# chip_mux_test.net
KiCad netlist of a schematic drawn in EAGLE
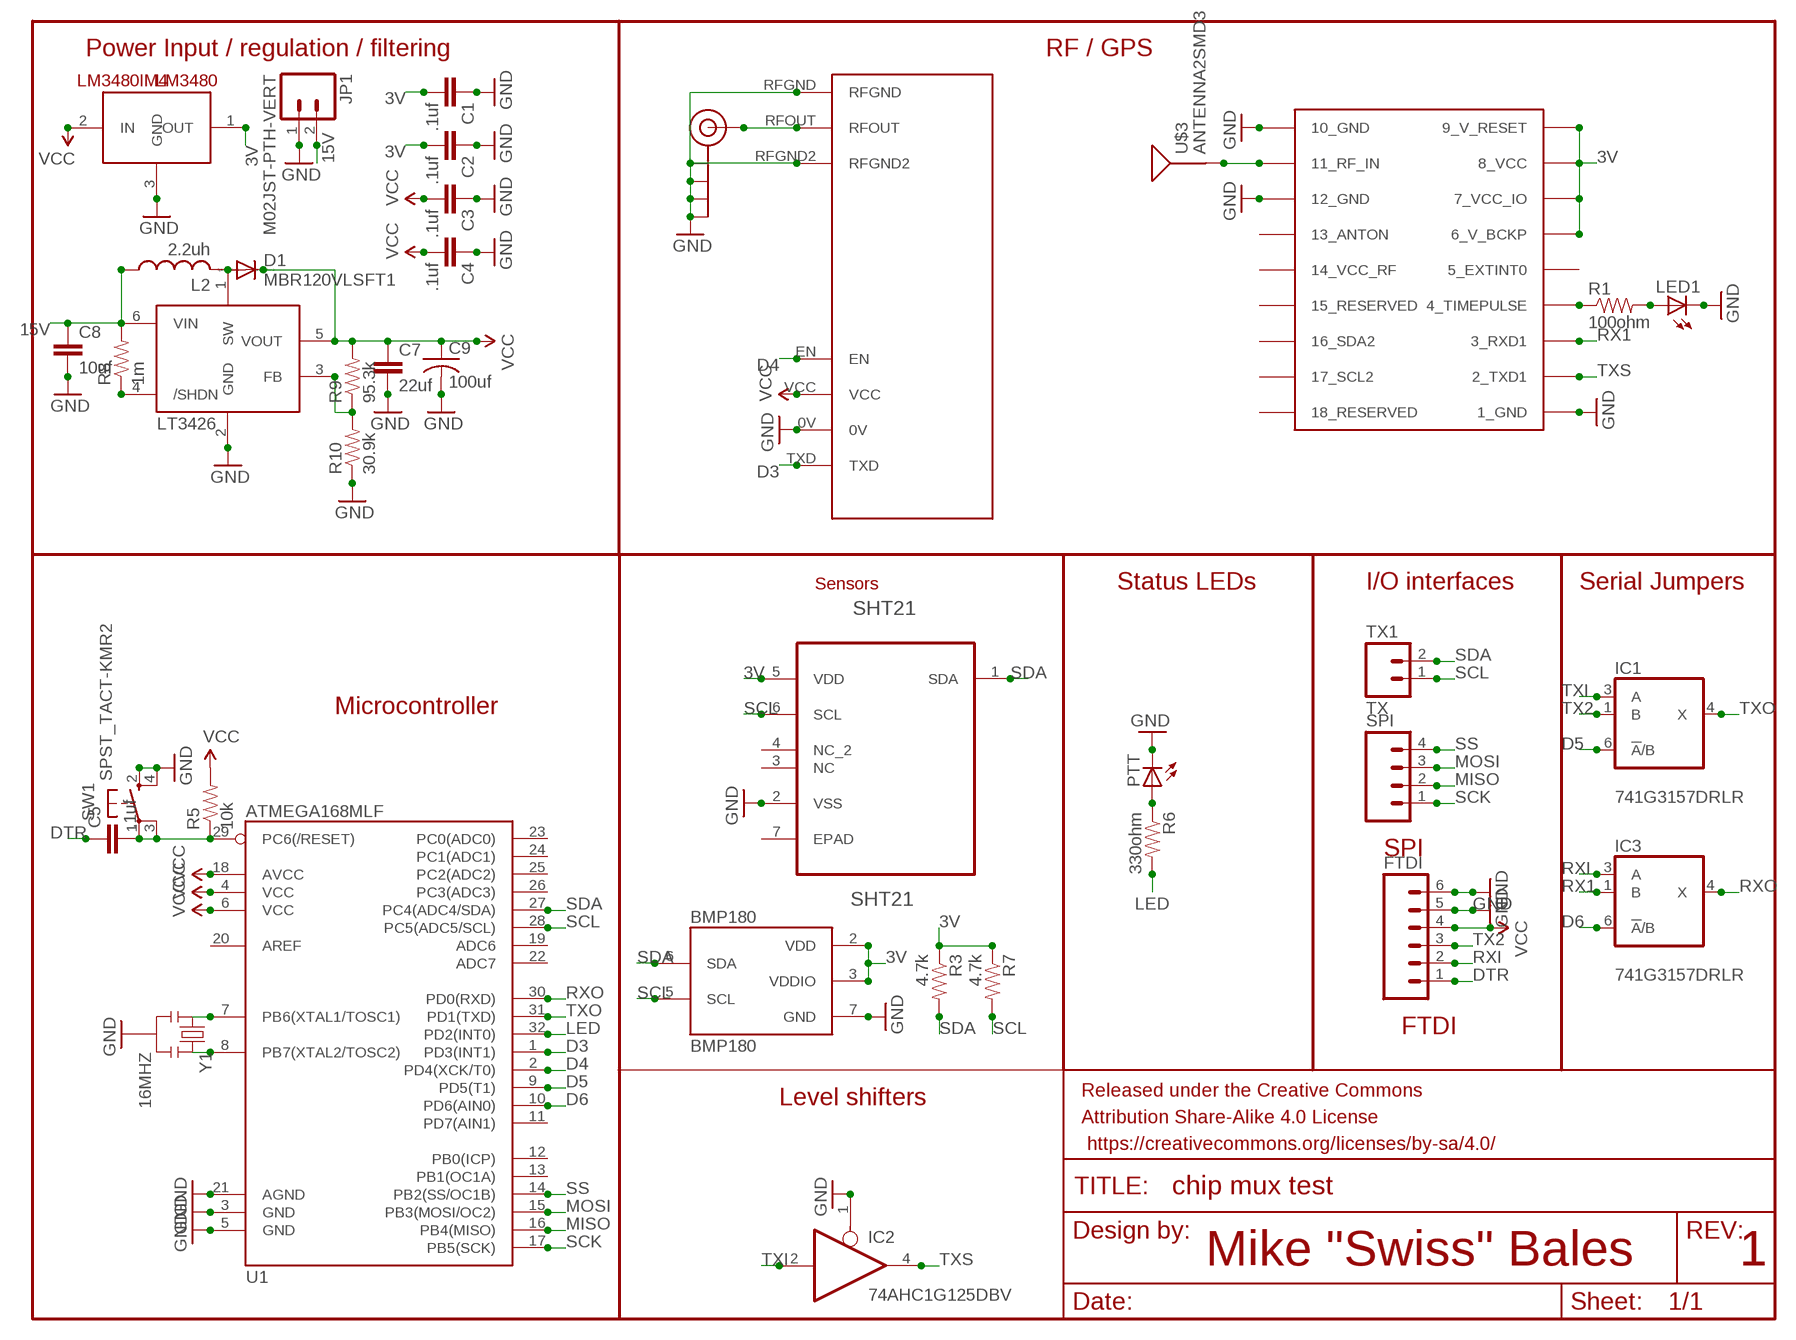
[diagram p0: schematic, sheet 1]

(export (version "E")
  (design (tool "Eeschema 10.0.6"))
  (components
    (comp (ref "BMP180")
      (value "BMP180")
      (footprint "eagle-import:BMP180")
      (libsource (lib "eagle-import") (part "BMP180"))
    )
    (comp (ref "C1")
      (value ".1uf")
      (footprint "eagle-import:0805")
      (libsource (lib "eagle-import") (part "CAP0805"))
    )
    (comp (ref "C2")
      (value ".1uf")
      (footprint "eagle-import:0805")
      (libsource (lib "eagle-import") (part "CAP0805"))
    )
    (comp (ref "C3")
      (value ".1uf")
      (footprint "eagle-import:0805")
      (libsource (lib "eagle-import") (part "CAP0805"))
    )
    (comp (ref "C4")
      (value ".1uf")
      (footprint "eagle-import:0805")
      (libsource (lib "eagle-import") (part "CAP0805"))
    )
    (comp (ref "C5")
      (value ".1uf")
      (footprint "eagle-import:0805")
      (libsource (lib "eagle-import") (part "CAP0805"))
    )
    (comp (ref "C7")
      (value "22uf")
      (footprint "eagle-import:0805")
      (libsource (lib "eagle-import") (part "CAP0805"))
    )
    (comp (ref "C8")
      (value "10uf")
      (footprint "eagle-import:0805")
      (libsource (lib "eagle-import") (part "CAP0805"))
    )
    (comp (ref "C9")
      (value "100uf")
      (footprint "eagle-import:C1206")
      (libsource (lib "eagle-import") (part "C-USC1206"))
    )
    (comp (ref "D1")
      (value "MBR120VLSFT1")
      (footprint "eagle-import:SOD123")
      (libsource (lib "eagle-import") (part "DIODE-SOD123"))
    )
    (comp (ref "FRAME1")
      (value "FRAME-LETTER")
      (footprint "eagle-import:CREATIVE_COMMONS")
      (libsource (lib "eagle-import") (part "FRAME-LETTER"))
    )
    (comp (ref "FTDI")
      (value "M06NO_SILK_FEMALE_PTH")
      (footprint "eagle-import:1X06_NO_SILK")
      (libsource (lib "eagle-import") (part "M06NO_SILK_FEMALE_PTH"))
    )
    (comp (ref "IC1")
      (value "741G3157DRLR")
      (footprint "eagle-import:DRL_R-PDSO-N6")
      (libsource (lib "eagle-import") (part "741G3157DRLR"))
    )
    (comp (ref "IC2")
      (value "74AHC1G125DBV")
      (footprint "eagle-import:SOT23-5")
      (libsource (lib "eagle-import") (part "741G125DBVAHC"))
    )
    (comp (ref "IC3")
      (value "741G3157DRLR")
      (footprint "eagle-import:DRL_R-PDSO-N6")
      (libsource (lib "eagle-import") (part "741G3157DRLR"))
    )
    (comp (ref "J$1")
      (value "SMA_EDGE")
      (footprint "eagle-import:SMA-EDGE")
      (libsource (lib "eagle-import") (part "SMA_EDGE"))
    )
    (comp (ref "JP1")
      (value "M02JST-PTH-VERT")
      (footprint "eagle-import:JST-2-PTH-VERT")
      (libsource (lib "eagle-import") (part "M02JST-PTH-VERT"))
    )
    (comp (ref "L2")
      (value "2.2uh")
      (footprint "eagle-import:L1812")
      (libsource (lib "eagle-import") (part "L-USL1812"))
    )
    (comp (ref "LED1")
      (value "LEDCHIP-LED0805")
      (footprint "eagle-import:CHIP-LED0805")
      (libsource (lib "eagle-import") (part "LEDCHIP-LED0805"))
    )
    (comp (ref "LM3480")
      (value "LM3480IM4")
      (footprint "eagle-import:SOT23-3")
      (libsource (lib "eagle-import") (part "LM3480IM4"))
    )
    (comp (ref "LT3426")
      (value "LT3426")
      (footprint "eagle-import:SOT23-6")
      (libsource (lib "eagle-import") (part "LT3426"))
    )
    (comp (ref "PTT")
      (value "LEDCHIP-LED0805")
      (footprint "eagle-import:CHIP-LED0805")
      (libsource (lib "eagle-import") (part "LEDCHIP-LED0805"))
    )
    (comp (ref "R1")
      (value "100ohm")
      (footprint "eagle-import:0805")
      (libsource (lib "eagle-import") (part "RESISTOR0805-RES"))
    )
    (comp (ref "R3")
      (value "4.7k")
      (footprint "eagle-import:0805")
      (libsource (lib "eagle-import") (part "RESISTOR0805-RES"))
    )
    (comp (ref "R5")
      (value "10k")
      (footprint "eagle-import:0805")
      (libsource (lib "eagle-import") (part "RESISTOR0805-RES"))
    )
    (comp (ref "R6")
      (value "330ohm")
      (footprint "eagle-import:0805")
      (libsource (lib "eagle-import") (part "RESISTOR0805-RES"))
    )
    (comp (ref "R7")
      (value "4.7k")
      (footprint "eagle-import:0805")
      (libsource (lib "eagle-import") (part "RESISTOR0805-RES"))
    )
    (comp (ref "R8")
      (value "1m")
      (footprint "eagle-import:0805")
      (libsource (lib "eagle-import") (part "RESISTOR0805-RES"))
    )
    (comp (ref "R9")
      (value "95.3k")
      (footprint "eagle-import:0805")
      (libsource (lib "eagle-import") (part "RESISTOR0805-RES"))
    )
    (comp (ref "R10")
      (value "30.9k")
      (footprint "eagle-import:0805")
      (libsource (lib "eagle-import") (part "RESISTOR0805-RES"))
    )
    (comp (ref "SHT21")
      (value "SHT21")
      (footprint "eagle-import:DFN300X300X110-7N")
      (libsource (lib "eagle-import") (part "SHT21"))
    )
    (comp (ref "SPI")
      (value "M04JST-PTH-VERT")
      (footprint "eagle-import:JST-4-PTH-VERT")
      (libsource (lib "eagle-import") (part "M04JST-PTH-VERT"))
    )
    (comp (ref "SW1")
      (value "SPST_TACT-KMR2")
      (footprint "eagle-import:KMR2")
      (libsource (lib "eagle-import") (part "SPST_TACT-KMR2"))
    )
    (comp (ref "TX1")
      (value "TX")
      (footprint "eagle-import:JST-2-PTH-VERT")
      (libsource (lib "eagle-import") (part "M02JST-PTH-VERT"))
    )
    (comp (ref "U$1")
      (value "UBLOX_MAX")
      (footprint "eagle-import:UBLOX_MAX")
      (libsource (lib "eagle-import") (part "UBLOX_MAX"))
    )
    (comp (ref "U$2")
      (value "RADIOMETRIX-HX1")
      (footprint "eagle-import:RADIOMETRIX-HX1")
      (libsource (lib "eagle-import") (part "RADIOMETRIX-HX1"))
    )
    (comp (ref "U$3")
      (value "ANTENNA2SMD3")
      (footprint "eagle-import:ANTENNA-CHIP4")
      (libsource (lib "eagle-import") (part "ANTENNA2SMD3"))
    )
    (comp (ref "U1")
      (value "ATMEGA168MLF")
      (footprint "eagle-import:MLF32")
      (libsource (lib "eagle-import") (part "ATMEGA168MLF"))
    )
    (comp (ref "Y1")
      (value "16MHZ")
      (footprint "eagle-import:RESONATOR-SMD")
      (libsource (lib "eagle-import") (part "RESONATOR16MHZ"))
    )
  )
  (nets
    (net (code "1") (name "/3V") (class "Default")
      (node (ref "BMP180") (pin "2") (pinfunction "VDD_2") (pintype "power_in"))
      (node (ref "BMP180") (pin "3") (pinfunction "VDDIO_3") (pintype "power_in"))
      (node (ref "C1") (pin "2") (pinfunction "2_2") (pintype "passive"))
      (node (ref "C2") (pin "2") (pinfunction "2_2") (pintype "passive"))
      (node (ref "LM3480") (pin "1") (pinfunction "OUT_1") (pintype "bidirectional"))
      (node (ref "R3") (pin "1") (pinfunction "1_1") (pintype "passive"))
      (node (ref "R7") (pin "1") (pinfunction "1_1") (pintype "passive"))
      (node (ref "SHT21") (pin "5") (pinfunction "VDD_5") (pintype "power_in"))
      (node (ref "U$1") (pin "6_V_BCKP") (pinfunction "6_V_BCKP_6_V_BCKP") (pintype "bidirectional"))
      (node (ref "U$1") (pin "7_VCC_IO") (pinfunction "7_VCC_IO_7_VCC_IO") (pintype "power_in"))
      (node (ref "U$1") (pin "8_VCC") (pinfunction "8_VCC_8_VCC") (pintype "power_in"))
      (node (ref "U$1") (pin "9_V_RESET") (pinfunction "9_V_RESET_9_V_RESET") (pintype "power_in"))
    )
    (net (code "2") (name "/15V") (class "Default")
      (node (ref "C8") (pin "1") (pinfunction "1_1") (pintype "passive"))
      (node (ref "JP1") (pin "2") (pinfunction "2_2") (pintype "passive"))
      (node (ref "L2") (pin "1") (pinfunction "1_1") (pintype "passive"))
      (node (ref "LT3426") (pin "6") (pinfunction "VIN_6") (pintype "input"))
      (node (ref "R8") (pin "2") (pinfunction "2_2") (pintype "passive"))
    )
    (net (code "3") (name "/D3") (class "Default")
      (node (ref "U$2") (pin "TXD") (pinfunction "TXD_TXD") (pintype "bidirectional"))
      (node (ref "U1") (pin "1") (pinfunction "PD3(INT1)_1") (pintype "bidirectional"))
    )
    (net (code "4") (name "/D4") (class "Default")
      (node (ref "U$2") (pin "EN") (pinfunction "EN_EN") (pintype "bidirectional"))
      (node (ref "U1") (pin "2") (pinfunction "PD4(XCK/T0)_2") (pintype "bidirectional"))
    )
    (net (code "5") (name "/D5") (class "Default")
      (node (ref "IC1") (pin "6") (pinfunction "~{A}/B_6") (pintype "input"))
      (node (ref "U1") (pin "9") (pinfunction "PD5(T1)_9") (pintype "bidirectional"))
    )
    (net (code "6") (name "/D6") (class "Default")
      (node (ref "IC3") (pin "6") (pinfunction "~{A}/B_6") (pintype "input"))
      (node (ref "U1") (pin "10") (pinfunction "PD6(AIN0)_10") (pintype "bidirectional"))
    )
    (net (code "7") (name "/DTR") (class "Default")
      (node (ref "C5") (pin "1") (pinfunction "1_1") (pintype "passive"))
      (node (ref "FTDI") (pin "1") (pinfunction "1_1") (pintype "passive"))
    )
    (net (code "8") (name "/LED") (class "Default")
      (node (ref "R6") (pin "2") (pinfunction "2_2") (pintype "passive"))
      (node (ref "U1") (pin "32") (pinfunction "PD2(INT0)_32") (pintype "bidirectional"))
    )
    (net (code "9") (name "/MISO") (class "Default")
      (node (ref "SPI") (pin "2") (pinfunction "2_2") (pintype "passive"))
      (node (ref "U1") (pin "16") (pinfunction "PB4(MISO)_16") (pintype "bidirectional"))
    )
    (net (code "10") (name "/MOSI") (class "Default")
      (node (ref "SPI") (pin "3") (pinfunction "3_3") (pintype "passive"))
      (node (ref "U1") (pin "15") (pinfunction "PB3(MOSI/OC2)_15") (pintype "bidirectional"))
    )
    (net (code "11") (name "/RX1") (class "Default")
      (node (ref "IC3") (pin "1") (pinfunction "B_1") (pintype "bidirectional"))
      (node (ref "U$1") (pin "3_RXD1") (pinfunction "3_RXD1_3_RXD1") (pintype "bidirectional"))
    )
    (net (code "12") (name "/RXI") (class "Default")
      (node (ref "FTDI") (pin "2") (pinfunction "2_2") (pintype "passive"))
      (node (ref "IC3") (pin "3") (pinfunction "A_3") (pintype "bidirectional"))
    )
    (net (code "13") (name "/RXO") (class "Default")
      (node (ref "IC3") (pin "4") (pinfunction "X_4") (pintype "bidirectional"))
      (node (ref "U1") (pin "30") (pinfunction "PD0(RXD)_30") (pintype "bidirectional"))
    )
    (net (code "14") (name "/SCK") (class "Default")
      (node (ref "SPI") (pin "1") (pinfunction "1_1") (pintype "passive"))
      (node (ref "U1") (pin "17") (pinfunction "PB5(SCK)_17") (pintype "bidirectional"))
    )
    (net (code "15") (name "/SCL") (class "Default")
      (node (ref "BMP180") (pin "5") (pinfunction "SCL_5") (pintype "input"))
      (node (ref "R7") (pin "2") (pinfunction "2_2") (pintype "passive"))
      (node (ref "SHT21") (pin "6") (pinfunction "SCL_6") (pintype "input"))
      (node (ref "TX1") (pin "1") (pinfunction "1_1") (pintype "passive"))
      (node (ref "U1") (pin "28") (pinfunction "PC5(ADC5/SCL)_28") (pintype "bidirectional"))
    )
    (net (code "16") (name "/SDA") (class "Default")
      (node (ref "BMP180") (pin "6") (pinfunction "SDA_6") (pintype "bidirectional"))
      (node (ref "R3") (pin "2") (pinfunction "2_2") (pintype "passive"))
      (node (ref "SHT21") (pin "1") (pinfunction "SDA_1") (pintype "bidirectional"))
      (node (ref "TX1") (pin "2") (pinfunction "2_2") (pintype "passive"))
      (node (ref "U1") (pin "27") (pinfunction "PC4(ADC4/SDA)_27") (pintype "bidirectional"))
    )
    (net (code "17") (name "/SS") (class "Default")
      (node (ref "SPI") (pin "4") (pinfunction "4_4") (pintype "passive"))
      (node (ref "U1") (pin "14") (pinfunction "PB2(SS/OC1B)_14") (pintype "bidirectional"))
    )
    (net (code "18") (name "/TX2") (class "Default")
      (node (ref "FTDI") (pin "3") (pinfunction "3_3") (pintype "passive"))
      (node (ref "IC1") (pin "1") (pinfunction "B_1") (pintype "bidirectional"))
    )
    (net (code "19") (name "/TXI") (class "Default")
      (node (ref "IC1") (pin "3") (pinfunction "A_3") (pintype "bidirectional"))
      (node (ref "IC2") (pin "2") (pinfunction "I_2") (pintype "input"))
    )
    (net (code "20") (name "/TXO") (class "Default")
      (node (ref "IC1") (pin "4") (pinfunction "X_4") (pintype "bidirectional"))
      (node (ref "U1") (pin "31") (pinfunction "PD1(TXD)_31") (pintype "bidirectional"))
    )
    (net (code "21") (name "/TXS") (class "Default")
      (node (ref "IC2") (pin "4") (pinfunction "O_4") (pintype "tri_state"))
      (node (ref "U$1") (pin "2_TXD1") (pinfunction "2_TXD1_2_TXD1") (pintype "bidirectional"))
    )
    (net (code "22") (name "GND") (class "Default")
      (node (ref "BMP180") (pin "7") (pinfunction "GND_7") (pintype "power_in"))
      (node (ref "C1") (pin "1") (pinfunction "1_1") (pintype "passive"))
      (node (ref "C2") (pin "1") (pinfunction "1_1") (pintype "passive"))
      (node (ref "C3") (pin "1") (pinfunction "1_1") (pintype "passive"))
      (node (ref "C4") (pin "1") (pinfunction "1_1") (pintype "passive"))
      (node (ref "C7") (pin "2") (pinfunction "2_2") (pintype "passive"))
      (node (ref "C8") (pin "2") (pinfunction "2_2") (pintype "passive"))
      (node (ref "C9") (pin "2") (pinfunction "2_2") (pintype "passive"))
      (node (ref "FTDI") (pin "5") (pinfunction "5_5") (pintype "passive"))
      (node (ref "FTDI") (pin "6") (pinfunction "6_6") (pintype "passive"))
      (node (ref "IC2") (pin "1") (pinfunction "OE_1") (pintype "input"))
      (node (ref "J$1") (pin "GND@0") (pinfunction "GND_GND@0") (pintype "bidirectional"))
      (node (ref "J$1") (pin "GND@1") (pinfunction "GND_GND@1") (pintype "bidirectional"))
      (node (ref "J$1") (pin "GND@2") (pinfunction "GND_GND@2") (pintype "bidirectional"))
      (node (ref "J$1") (pin "GND@3") (pinfunction "GND_GND@3") (pintype "bidirectional"))
      (node (ref "JP1") (pin "1") (pinfunction "1_1") (pintype "passive"))
      (node (ref "LED1") (pin "C") (pinfunction "C_C") (pintype "passive"))
      (node (ref "LM3480") (pin "3") (pinfunction "GND_3") (pintype "bidirectional"))
      (node (ref "LT3426") (pin "2") (pinfunction "GND_2") (pintype "power_in"))
      (node (ref "PTT") (pin "C") (pinfunction "C_C") (pintype "passive"))
      (node (ref "R10") (pin "1") (pinfunction "1_1") (pintype "passive"))
      (node (ref "SHT21") (pin "2") (pinfunction "VSS_2") (pintype "power_in"))
      (node (ref "SW1") (pin "2") (pinfunction "S_2") (pintype "passive"))
      (node (ref "SW1") (pin "4") (pinfunction "S1_4") (pintype "passive"))
      (node (ref "U$1") (pin "10_GND") (pinfunction "10_GND_10_GND") (pintype "power_in"))
      (node (ref "U$1") (pin "12_GND") (pinfunction "12_GND_12_GND") (pintype "power_in"))
      (node (ref "U$1") (pin "1_GND") (pinfunction "1_GND_1_GND") (pintype "power_in"))
      (node (ref "U$2") (pin "0V") (pinfunction "0V_0V") (pintype "bidirectional"))
      (node (ref "U$2") (pin "RFGND") (pinfunction "RFGND_RFGND") (pintype "bidirectional"))
      (node (ref "U$2") (pin "RFGND2") (pinfunction "RFGND2_RFGND2") (pintype "bidirectional"))
      (node (ref "U1") (pin "21") (pinfunction "AGND_21") (pintype "bidirectional"))
      (node (ref "U1") (pin "3") (pinfunction "GND_3") (pintype "bidirectional"))
      (node (ref "U1") (pin "5") (pinfunction "GND_5") (pintype "bidirectional"))
      (node (ref "Y1") (pin "2") (pinfunction "2_2") (pintype "passive"))
    )
    (net (code "23") (name "Net-(J$1-SIGNAL)") (class "Default")
      (node (ref "J$1") (pin "SIG") (pinfunction "SIGNAL_SIG") (pintype "bidirectional"))
      (node (ref "U$2") (pin "RFOUT") (pinfunction "RFOUT_RFOUT") (pintype "bidirectional"))
    )
    (net (code "24") (name "Net-(LED1-PadA)") (class "Default")
      (node (ref "LED1") (pin "A") (pinfunction "A_A") (pintype "passive"))
      (node (ref "R1") (pin "2") (pinfunction "2_2") (pintype "passive"))
    )
    (net (code "25") (name "Net-(LT3426-FB)") (class "Default")
      (node (ref "LT3426") (pin "3") (pinfunction "FB_3") (pintype "input"))
      (node (ref "R10") (pin "2") (pinfunction "2_2") (pintype "passive"))
      (node (ref "R9") (pin "1") (pinfunction "1_1") (pintype "passive"))
    )
    (net (code "26") (name "Net-(LT3426-SW)") (class "Default")
      (node (ref "D1") (pin "A") (pinfunction "A_A") (pintype "passive"))
      (node (ref "L2") (pin "2") (pinfunction "2_2") (pintype "passive"))
      (node (ref "LT3426") (pin "1") (pinfunction "SW_1") (pintype "output"))
    )
    (net (code "27") (name "Net-(LT3426-{slash}SHDN)") (class "Default")
      (node (ref "LT3426") (pin "4") (pinfunction "/SHDN_4") (pintype "input"))
      (node (ref "R8") (pin "1") (pinfunction "1_1") (pintype "passive"))
    )
    (net (code "28") (name "Net-(PTT-PadA)") (class "Default")
      (node (ref "PTT") (pin "A") (pinfunction "A_A") (pintype "passive"))
      (node (ref "R6") (pin "1") (pinfunction "1_1") (pintype "passive"))
    )
    (net (code "29") (name "Net-(R1-Pad1)") (class "Default")
      (node (ref "R1") (pin "1") (pinfunction "1_1") (pintype "passive"))
      (node (ref "U$1") (pin "4_TIMEPULSE") (pinfunction "4_TIMEPULSE_4_TIMEPULSE") (pintype "bidirectional"))
    )
    (net (code "30") (name "Net-(SW1-P)") (class "Default")
      (node (ref "C5") (pin "2") (pinfunction "2_2") (pintype "passive"))
      (node (ref "R5") (pin "1") (pinfunction "1_1") (pintype "passive"))
      (node (ref "SW1") (pin "1") (pinfunction "P_1") (pintype "passive"))
      (node (ref "SW1") (pin "3") (pinfunction "P1_3") (pintype "passive"))
      (node (ref "U1") (pin "29") (pinfunction "PC6(/RESET)_29") (pintype "bidirectional"))
    )
    (net (code "31") (name "Net-(U$3-SIGNAL)") (class "Default")
      (node (ref "U$1") (pin "11_RF_IN") (pinfunction "11_RF_IN_11_RF_IN") (pintype "bidirectional"))
      (node (ref "U$3") (pin "SIG") (pinfunction "SIGNAL_SIG") (pintype "bidirectional"))
    )
    (net (code "32") (name "Net-(U1-PB6(XTAL1{slash}TOSC1))") (class "Default")
      (node (ref "U1") (pin "7") (pinfunction "PB6(XTAL1/TOSC1)_7") (pintype "bidirectional"))
      (node (ref "Y1") (pin "1") (pinfunction "1_1") (pintype "passive"))
    )
    (net (code "33") (name "Net-(U1-PB7(XTAL2{slash}TOSC2))") (class "Default")
      (node (ref "U1") (pin "8") (pinfunction "PB7(XTAL2/TOSC2)_8") (pintype "bidirectional"))
      (node (ref "Y1") (pin "3") (pinfunction "3_3") (pintype "passive"))
    )
    (net (code "34") (name "VCC") (class "Default")
      (node (ref "C3") (pin "2") (pinfunction "2_2") (pintype "passive"))
      (node (ref "C4") (pin "2") (pinfunction "2_2") (pintype "passive"))
      (node (ref "C7") (pin "1") (pinfunction "1_1") (pintype "passive"))
      (node (ref "C9") (pin "1") (pinfunction "1_1") (pintype "passive"))
      (node (ref "D1") (pin "C") (pinfunction "C_C") (pintype "passive"))
      (node (ref "FTDI") (pin "4") (pinfunction "4_4") (pintype "passive"))
      (node (ref "LM3480") (pin "2") (pinfunction "IN_2") (pintype "bidirectional"))
      (node (ref "LT3426") (pin "5") (pinfunction "VOUT_5") (pintype "output"))
      (node (ref "R5") (pin "2") (pinfunction "2_2") (pintype "passive"))
      (node (ref "R9") (pin "2") (pinfunction "2_2") (pintype "passive"))
      (node (ref "U$2") (pin "VCC") (pinfunction "VCC_VCC") (pintype "bidirectional"))
      (node (ref "U1") (pin "18") (pinfunction "AVCC_18") (pintype "bidirectional"))
      (node (ref "U1") (pin "4") (pinfunction "VCC_4") (pintype "bidirectional"))
      (node (ref "U1") (pin "6") (pinfunction "VCC_6") (pintype "bidirectional"))
    )
    (net (code "35") (name "unconnected-(SHT21-EPAD-Pad7)") (class "Default")
      (node (ref "SHT21") (pin "7") (pinfunction "EPAD_7") (pintype "passive"))
    )
    (net (code "36") (name "unconnected-(SHT21-NC-Pad3)") (class "Default")
      (node (ref "SHT21") (pin "3") (pinfunction "NC_3") (pintype "no_connect"))
    )
    (net (code "37") (name "unconnected-(SHT21-NC_2-Pad4)") (class "Default")
      (node (ref "SHT21") (pin "4") (pinfunction "NC_2_4") (pintype "no_connect"))
    )
    (net (code "38") (name "unconnected-(U$1-Pad5_EXTINT0)") (class "Default")
      (node (ref "U$1") (pin "5_EXTINT0") (pinfunction "5_EXTINT0_5_EXTINT0") (pintype "bidirectional"))
    )
    (net (code "39") (name "unconnected-(U$1-Pad13_ANTON)") (class "Default")
      (node (ref "U$1") (pin "13_ANTON") (pinfunction "13_ANTON_13_ANTON") (pintype "bidirectional"))
    )
    (net (code "40") (name "unconnected-(U$1-Pad14_VCC_RF)") (class "Default")
      (node (ref "U$1") (pin "14_VCC_RF") (pinfunction "14_VCC_RF_14_VCC_RF") (pintype "bidirectional"))
    )
    (net (code "41") (name "unconnected-(U$1-Pad15_RESERVED)") (class "Default")
      (node (ref "U$1") (pin "15_RESERVED") (pinfunction "15_RESERVED_15_RESERVED") (pintype "bidirectional"))
    )
    (net (code "42") (name "unconnected-(U$1-Pad16_SDA2)") (class "Default")
      (node (ref "U$1") (pin "16_SDA2") (pinfunction "16_SDA2_16_SDA2") (pintype "bidirectional"))
    )
    (net (code "43") (name "unconnected-(U$1-Pad17_SCL2)") (class "Default")
      (node (ref "U$1") (pin "17_SCL2") (pinfunction "17_SCL2_17_SCL2") (pintype "bidirectional"))
    )
    (net (code "44") (name "unconnected-(U$1-Pad18_RESERVED)") (class "Default")
      (node (ref "U$1") (pin "18_RESERVED") (pinfunction "18_RESERVED_18_RESERVED") (pintype "bidirectional"))
    )
    (net (code "45") (name "unconnected-(U1-ADC6-Pad19)") (class "Default")
      (node (ref "U1") (pin "19") (pinfunction "ADC6_19") (pintype "bidirectional"))
    )
    (net (code "46") (name "unconnected-(U1-ADC7-Pad22)") (class "Default")
      (node (ref "U1") (pin "22") (pinfunction "ADC7_22") (pintype "bidirectional"))
    )
    (net (code "47") (name "unconnected-(U1-AREF-Pad20)") (class "Default")
      (node (ref "U1") (pin "20") (pinfunction "AREF_20") (pintype "bidirectional"))
    )
    (net (code "48") (name "unconnected-(U1-PB0(ICP)-Pad12)") (class "Default")
      (node (ref "U1") (pin "12") (pinfunction "PB0(ICP)_12") (pintype "bidirectional"))
    )
    (net (code "49") (name "unconnected-(U1-PB1(OC1A)-Pad13)") (class "Default")
      (node (ref "U1") (pin "13") (pinfunction "PB1(OC1A)_13") (pintype "bidirectional"))
    )
    (net (code "50") (name "unconnected-(U1-PC0(ADC0)-Pad23)") (class "Default")
      (node (ref "U1") (pin "23") (pinfunction "PC0(ADC0)_23") (pintype "bidirectional"))
    )
    (net (code "51") (name "unconnected-(U1-PC1(ADC1)-Pad24)") (class "Default")
      (node (ref "U1") (pin "24") (pinfunction "PC1(ADC1)_24") (pintype "bidirectional"))
    )
    (net (code "52") (name "unconnected-(U1-PC2(ADC2)-Pad25)") (class "Default")
      (node (ref "U1") (pin "25") (pinfunction "PC2(ADC2)_25") (pintype "bidirectional"))
    )
    (net (code "53") (name "unconnected-(U1-PC3(ADC3)-Pad26)") (class "Default")
      (node (ref "U1") (pin "26") (pinfunction "PC3(ADC3)_26") (pintype "bidirectional"))
    )
    (net (code "54") (name "unconnected-(U1-PD7(AIN1)-Pad11)") (class "Default")
      (node (ref "U1") (pin "11") (pinfunction "PD7(AIN1)_11") (pintype "bidirectional"))
    )
  )
)
